# IR.net
KiCad netlist of a schematic drawn in Altium Designer
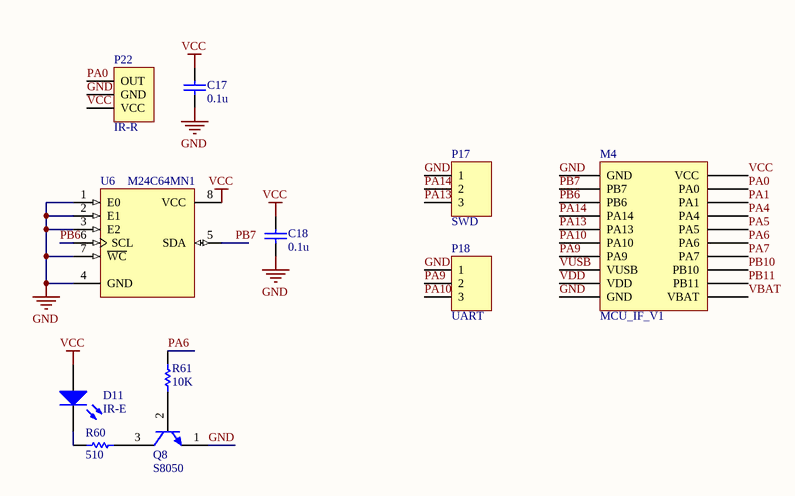
[diagram p0: IR.SchDoc]

(export (version "E")
  (design (tool "Eeschema 10.0.6"))
  (components
    (comp (ref "C17")
      (value "0.1u")
      (footprint "C-1608[0603]")
      (description "Capacitor (Semiconductor SIM Model)")
      (fields (field (name "Comment") "Cap Semi") (field (name "PUBLISHER") "Altium Limited"))
      (libsource (lib "Miscellaneous Devices") (part "Cap Semi"))
    )
    (comp (ref "C18")
      (value "0.1u")
      (footprint "C-1608[0603]")
      (description "Capacitor (Semiconductor SIM Model)")
      (fields (field (name "Comment") "Cap Semi") (field (name "PUBLISHER") "Altium Limited"))
      (libsource (lib "Miscellaneous Devices") (part "Cap Semi"))
    )
    (comp (ref "D11")
      (value "IR-E")
      (footprint "PIN2")
      (description "Typical INFRARED GaAs LED")
      (fields (field (name "PUBLISHER") "Altium Limited"))
      (libsource (lib "Miscellaneous Devices") (part "LED0"))
    )
    (comp (ref "M4")
      (value "MCU_IF_V1")
      (footprint "MCU_IF_V1")
      (libsource (lib "MCU_IF") (part "MCU_IF_V1"))
    )
    (comp (ref "P17")
      (value "SWD")
      (footprint "HDR1X3")
      (description "Header, 3-Pin")
      (fields (field (name "PUBLISHER") "Altium Limited"))
      (libsource (lib "Miscellaneous Connectors") (part "Header 3"))
    )
    (comp (ref "P18")
      (value "UART")
      (footprint "HDR1X3")
      (description "Header, 3-Pin")
      (fields (field (name "PUBLISHER") "Altium Limited"))
      (libsource (lib "Miscellaneous Connectors") (part "Header 3"))
    )
    (comp (ref "P22")
      (value "IR-R")
      (footprint "HDR1X3")
      (description "Header, 3-Pin")
      (fields (field (name "PUBLISHER") "Altium Limited"))
      (libsource (lib "sensor_ifce") (part "IR"))
    )
    (comp (ref "Q8")
      (value "S8050")
      (footprint "SOT23B")
      (description "NPN General Purpose Amplifier")
      (fields (field (name "PUBLISHER") "Altium Limited"))
      (libsource (lib "Miscellaneous Devices") (part "2N3904"))
    )
    (comp (ref "R60")
      (value "510")
      (footprint "R-1608[0603]")
      (description "Semiconductor Resistor")
      (fields (field (name "Comment") "Res Semi") (field (name "PUBLISHER") "Altium Limited"))
      (libsource (lib "Miscellaneous Devices") (part "Res Semi"))
    )
    (comp (ref "R61")
      (value "10K")
      (footprint "R-1608[0603]")
      (description "Semiconductor Resistor")
      (fields (field (name "Comment") "Res Semi") (field (name "PUBLISHER") "Altium Limited"))
      (libsource (lib "Miscellaneous Devices") (part "Res Semi"))
    )
    (comp (ref "U6")
      (value "M24C64MN1")
      (footprint "SOP8_N")
      (description "64 Kbit Serial I²C Bus EEPROM")
      (fields (field (name "PUBLISHER") "Altium Limited"))
      (libsource (lib "ST Memory EEPROM Serial") (part "M24C64MN1"))
    )
  )
  (nets
    (net (code "1") (name "/PA0") (class "Default")
      (node (ref "M4") (pin "19") (pinfunction "PA0_19") (pintype "passive"))
      (node (ref "P22") (pin "1") (pinfunction "OUT_1") (pintype "passive"))
    )
    (net (code "2") (name "/PA1") (class "Default")
      (node (ref "M4") (pin "18") (pinfunction "PA1_18") (pintype "passive"))
    )
    (net (code "3") (name "/PA4") (class "Default")
      (node (ref "M4") (pin "17") (pinfunction "PA4_17") (pintype "passive"))
    )
    (net (code "4") (name "/PA5") (class "Default")
      (node (ref "M4") (pin "16") (pinfunction "PA5_16") (pintype "passive"))
    )
    (net (code "5") (name "/PA6") (class "Default")
      (node (ref "M4") (pin "15") (pinfunction "PA6_15") (pintype "passive"))
      (node (ref "R61") (pin "2") (pinfunction "2_2") (pintype "passive"))
    )
    (net (code "6") (name "/PA7") (class "Default")
      (node (ref "M4") (pin "14") (pinfunction "PA7_14") (pintype "passive"))
    )
    (net (code "7") (name "/PA9") (class "Default")
      (node (ref "M4") (pin "7") (pinfunction "PA9_7") (pintype "passive"))
      (node (ref "P18") (pin "2") (pinfunction "2_2") (pintype "passive"))
    )
    (net (code "8") (name "/PA10") (class "Default")
      (node (ref "M4") (pin "6") (pinfunction "PA10_6") (pintype "passive"))
      (node (ref "P18") (pin "3") (pinfunction "3_3") (pintype "passive"))
    )
    (net (code "9") (name "/PA13") (class "Default")
      (node (ref "M4") (pin "5") (pinfunction "PA13_5") (pintype "passive"))
      (node (ref "P17") (pin "3") (pinfunction "3_3") (pintype "passive"))
    )
    (net (code "10") (name "/PA14") (class "Default")
      (node (ref "M4") (pin "4") (pinfunction "PA14_4") (pintype "passive"))
      (node (ref "P17") (pin "2") (pinfunction "2_2") (pintype "passive"))
    )
    (net (code "11") (name "/PB6") (class "Default")
      (node (ref "M4") (pin "3") (pinfunction "PB6_3") (pintype "passive"))
      (node (ref "U6") (pin "6") (pinfunction "SCL_6") (pintype "input"))
    )
    (net (code "12") (name "/PB7") (class "Default")
      (node (ref "M4") (pin "2") (pinfunction "PB7_2") (pintype "passive"))
      (node (ref "U6") (pin "5") (pinfunction "SDA_5") (pintype "bidirectional"))
    )
    (net (code "13") (name "/PB10") (class "Default")
      (node (ref "M4") (pin "13") (pinfunction "PB10_13") (pintype "passive"))
    )
    (net (code "14") (name "/PB11") (class "Default")
      (node (ref "M4") (pin "12") (pinfunction "PB11_12") (pintype "passive"))
    )
    (net (code "15") (name "/VBAT") (class "Default")
      (node (ref "M4") (pin "11") (pinfunction "VBAT_11") (pintype "passive"))
    )
    (net (code "16") (name "/VDD") (class "Default")
      (node (ref "M4") (pin "9") (pinfunction "VDD_9") (pintype "passive"))
    )
    (net (code "17") (name "/VUSB") (class "Default")
      (node (ref "M4") (pin "8") (pinfunction "VUSB_8") (pintype "passive"))
    )
    (net (code "18") (name "GND") (class "Default")
      (node (ref "C17") (pin "1") (pinfunction "1_1") (pintype "passive"))
      (node (ref "C18") (pin "1") (pinfunction "1_1") (pintype "passive"))
      (node (ref "M4") (pin "1") (pinfunction "GND_1") (pintype "passive"))
      (node (ref "M4") (pin "10") (pinfunction "GND_10") (pintype "passive"))
      (node (ref "P17") (pin "1") (pinfunction "1_1") (pintype "passive"))
      (node (ref "P18") (pin "1") (pinfunction "1_1") (pintype "passive"))
      (node (ref "P22") (pin "2") (pinfunction "GND_2") (pintype "passive"))
      (node (ref "Q8") (pin "1") (pinfunction "E_1") (pintype "passive"))
      (node (ref "U6") (pin "1") (pinfunction "E0_1") (pintype "input"))
      (node (ref "U6") (pin "2") (pinfunction "E1_2") (pintype "input"))
      (node (ref "U6") (pin "3") (pinfunction "E2_3") (pintype "input"))
      (node (ref "U6") (pin "4") (pinfunction "GND_4") (pintype "power_in"))
      (node (ref "U6") (pin "7") (pinfunction "~{WC}_7") (pintype "input"))
    )
    (net (code "19") (name "Net-(D11-K)") (class "Default")
      (node (ref "D11") (pin "2") (pinfunction "K_2") (pintype "passive"))
      (node (ref "R60") (pin "1") (pinfunction "1_1") (pintype "passive"))
    )
    (net (code "20") (name "Net-(Q8-B)") (class "Default")
      (node (ref "Q8") (pin "2") (pinfunction "B_2") (pintype "passive"))
      (node (ref "R61") (pin "1") (pinfunction "1_1") (pintype "passive"))
    )
    (net (code "21") (name "Net-(Q8-C)") (class "Default")
      (node (ref "Q8") (pin "3") (pinfunction "C_3") (pintype "passive"))
      (node (ref "R60") (pin "2") (pinfunction "2_2") (pintype "passive"))
    )
    (net (code "22") (name "VCC") (class "Default")
      (node (ref "C17") (pin "2") (pinfunction "2_2") (pintype "passive"))
      (node (ref "C18") (pin "2") (pinfunction "2_2") (pintype "passive"))
      (node (ref "D11") (pin "1") (pinfunction "A_1") (pintype "passive"))
      (node (ref "M4") (pin "20") (pinfunction "VCC_20") (pintype "passive"))
      (node (ref "P22") (pin "3") (pinfunction "VCC_3") (pintype "passive"))
      (node (ref "U6") (pin "8") (pinfunction "VCC_8") (pintype "power_in"))
    )
  )
)
